# Voltage_Source.net
KiCad netlist of a schematic drawn in Altium Designer
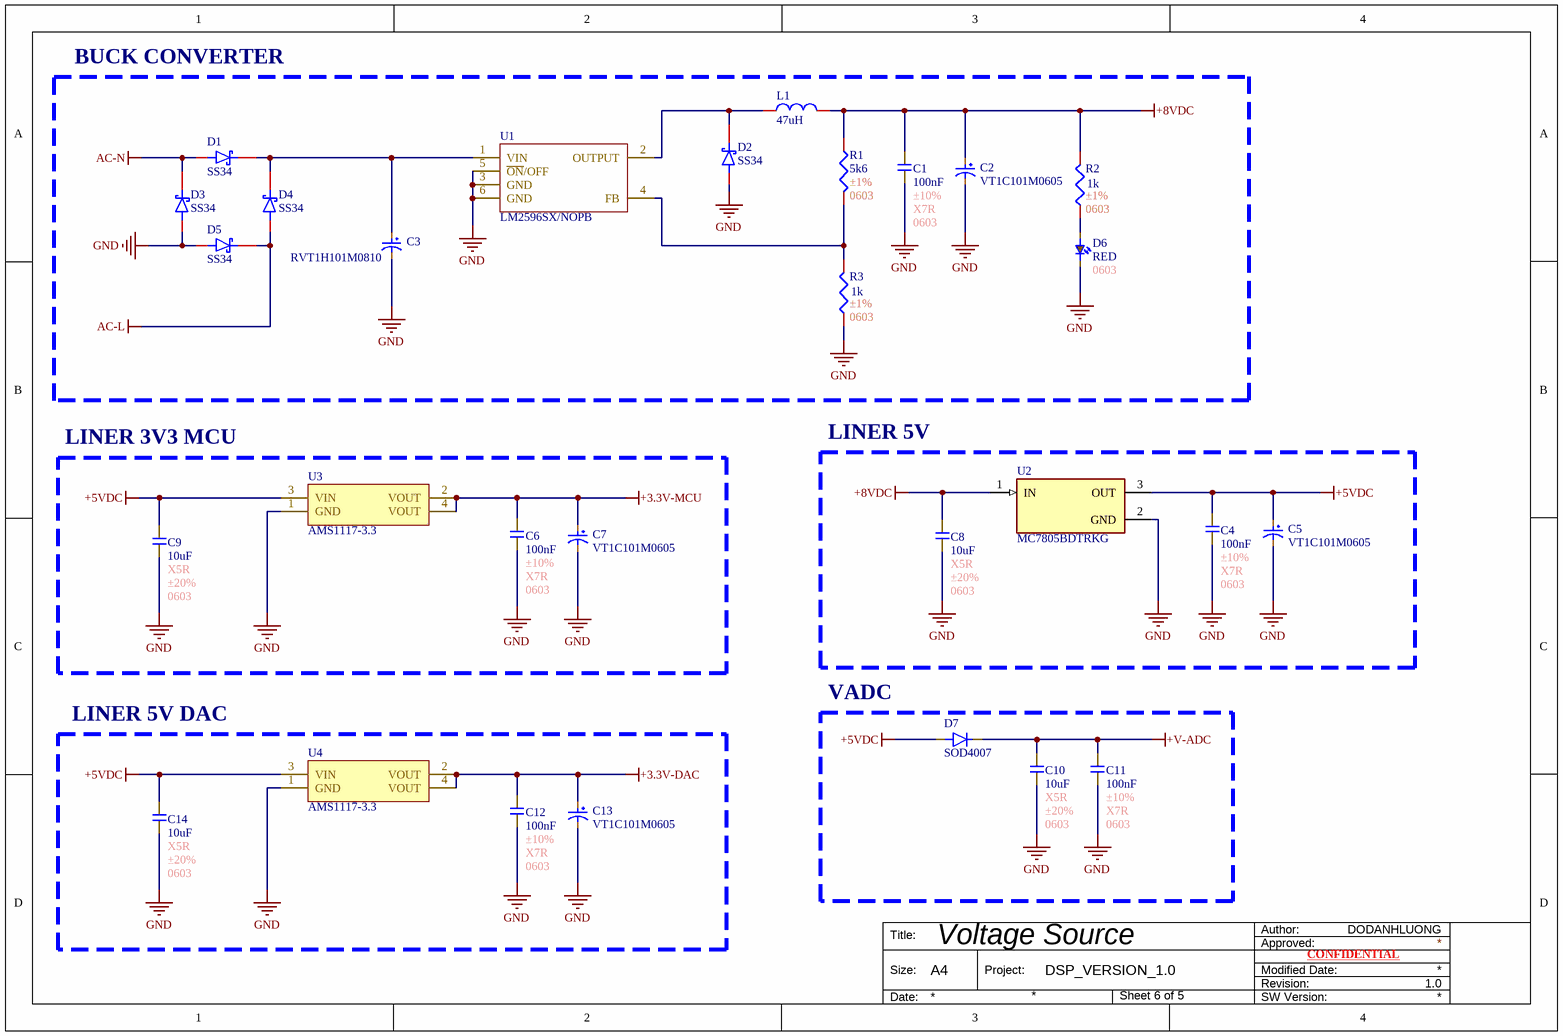
[diagram p0: Voltage Source.SchDoc]

(export (version "E")
  (design (tool "Eeschema 10.0.6"))
  (components
    (comp (ref "C1")
      (value "100nF")
      (footprint "C0603")
      (description "50V 100nF X7R ±10% 0603 Multilayer Ceramic Capacitors MLCC - SMD/SMT ROHS")
      (fields
        (field (name "MANUFACTURER") "YAGEO")
        (field (name "MFR. PART #") "CC0603KRX7R9BB104")
        (field (name "TOLERANCE") "±10%")
        (field (name "TEMPERATURE COEFFICIENT") "X7R")
        (field (name "PACKAGE") "0603")
      )
      (libsource (lib "DSP_VERSION_1.0") (part "C0603_100nF_±10%_X7R"))
    )
    (comp (ref "C2")
      (value "VT1C101M0605")
      (footprint "C_100uF_16V_Aluminum")
      (description "100uF 16V ±20% 63mA@120Hz SMD,D6.3xL5.4mm Aluminum Electrolytic Capacitors RoHS")
      (fields (field (name "MANUFACTURER") "ROQANG") (field (name "LCSC PART #") "C90273"))
      (libsource (lib "Capital") (part "C_100uF_16V_aluminum"))
    )
    (comp (ref "C3")
      (value "RVT1H101M0810")
      (footprint "C_100uF_Aluminum")
      (description "100uF 50V ±20% 146mA@120Hz SMD,D8xL10.2mm Aluminum Electrolytic Capacitors RoHS")
      (fields (field (name "MANUFACTURER") "ROQANG") (field (name "LCSC PART #") "C72480"))
      (libsource (lib "Capital") (part "C_100uF_aluminum"))
    )
    (comp (ref "C4")
      (value "100nF")
      (footprint "C0603")
      (description "50V 100nF X7R ±10% 0603 Multilayer Ceramic Capacitors MLCC - SMD/SMT ROHS")
      (fields
        (field (name "MANUFACTURER") "YAGEO")
        (field (name "MFR. PART #") "CC0603KRX7R9BB104")
        (field (name "TOLERANCE") "±10%")
        (field (name "TEMPERATURE COEFFICIENT") "X7R")
        (field (name "PACKAGE") "0603")
      )
      (libsource (lib "DSP_VERSION_1.0") (part "C0603_100nF_±10%_X7R"))
    )
    (comp (ref "C5")
      (value "VT1C101M0605")
      (footprint "C_100uF_16V_Aluminum")
      (description "100uF 16V ±20% 63mA@120Hz SMD,D6.3xL5.4mm Aluminum Electrolytic Capacitors RoHS")
      (fields (field (name "MANUFACTURER") "ROQANG") (field (name "LCSC PART #") "C90273"))
      (libsource (lib "Capital") (part "C_100uF_16V_aluminum"))
    )
    (comp (ref "C6")
      (value "100nF")
      (footprint "C0603")
      (description "50V 100nF X7R ±10% 0603 Multilayer Ceramic Capacitors MLCC - SMD/SMT ROHS")
      (fields
        (field (name "MANUFACTURER") "YAGEO")
        (field (name "MFR. PART #") "CC0603KRX7R9BB104")
        (field (name "TOLERANCE") "±10%")
        (field (name "TEMPERATURE COEFFICIENT") "X7R")
        (field (name "PACKAGE") "0603")
      )
      (libsource (lib "DSP_VERSION_1.0") (part "C0603_100nF_±10%_X7R"))
    )
    (comp (ref "C7")
      (value "VT1C101M0605")
      (footprint "C_100uF_16V_Aluminum")
      (description "100uF 16V ±20% 63mA@120Hz SMD,D6.3xL5.4mm Aluminum Electrolytic Capacitors RoHS")
      (fields (field (name "MANUFACTURER") "ROQANG") (field (name "LCSC PART #") "C90273"))
      (libsource (lib "Capital") (part "C_100uF_16V_aluminum"))
    )
    (comp (ref "C8")
      (value "10uF")
      (footprint "C0603")
      (description "25V 10uF X5R ±20% 0603 Multilayer Ceramic Capacitors MLCC - SMD/SMT ROHS")
      (fields
        (field (name "MANUFACTURER") "YAGEO")
        (field (name "MFR. PART #") "CC0603MRX5R8BB106")
        (field (name "TEMPERATURE COEFFICIENT") "X5R")
        (field (name "TOLERANCE") "±20%")
        (field (name "PACKAGE") "0603")
      )
      (libsource (lib "DSP_VERSION_1.0") (part "C0603_10uF_±10%_X7R"))
    )
    (comp (ref "C9")
      (value "10uF")
      (footprint "C0603")
      (description "25V 10uF X5R ±20% 0603 Multilayer Ceramic Capacitors MLCC - SMD/SMT ROHS")
      (fields
        (field (name "MANUFACTURER") "YAGEO")
        (field (name "MFR. PART #") "CC0603MRX5R8BB106")
        (field (name "TEMPERATURE COEFFICIENT") "X5R")
        (field (name "TOLERANCE") "±20%")
        (field (name "PACKAGE") "0603")
      )
      (libsource (lib "DSP_VERSION_1.0") (part "C0603_10uF_±10%_X7R"))
    )
    (comp (ref "C10")
      (value "10uF")
      (footprint "C0603")
      (description "25V 10uF X5R ±20% 0603 Multilayer Ceramic Capacitors MLCC - SMD/SMT ROHS")
      (fields
        (field (name "MANUFACTURER") "YAGEO")
        (field (name "MFR. PART #") "CC0603MRX5R8BB106")
        (field (name "TEMPERATURE COEFFICIENT") "X5R")
        (field (name "TOLERANCE") "±20%")
        (field (name "PACKAGE") "0603")
      )
      (libsource (lib "DSP_VERSION_1.0") (part "C0603_10uF_±10%_X7R"))
    )
    (comp (ref "C11")
      (value "100nF")
      (footprint "C0603")
      (description "50V 100nF X7R ±10% 0603 Multilayer Ceramic Capacitors MLCC - SMD/SMT ROHS")
      (fields
        (field (name "MANUFACTURER") "YAGEO")
        (field (name "MFR. PART #") "CC0603KRX7R9BB104")
        (field (name "TOLERANCE") "±10%")
        (field (name "TEMPERATURE COEFFICIENT") "X7R")
        (field (name "PACKAGE") "0603")
      )
      (libsource (lib "DSP_VERSION_1.0") (part "C0603_100nF_±10%_X7R"))
    )
    (comp (ref "C12")
      (value "100nF")
      (footprint "C0603")
      (description "50V 100nF X7R ±10% 0603 Multilayer Ceramic Capacitors MLCC - SMD/SMT ROHS")
      (fields
        (field (name "MANUFACTURER") "YAGEO")
        (field (name "MFR. PART #") "CC0603KRX7R9BB104")
        (field (name "TOLERANCE") "±10%")
        (field (name "TEMPERATURE COEFFICIENT") "X7R")
        (field (name "PACKAGE") "0603")
      )
      (libsource (lib "DSP_VERSION_1.0") (part "C0603_100nF_±10%_X7R"))
    )
    (comp (ref "C13")
      (value "VT1C101M0605")
      (footprint "C_100uF_16V_Aluminum")
      (description "100uF 16V ±20% 63mA@120Hz SMD,D6.3xL5.4mm Aluminum Electrolytic Capacitors RoHS")
      (fields (field (name "MANUFACTURER") "ROQANG") (field (name "LCSC PART #") "C90273"))
      (libsource (lib "Capital") (part "C_100uF_16V_aluminum"))
    )
    (comp (ref "C14")
      (value "10uF")
      (footprint "C0603")
      (description "25V 10uF X5R ±20% 0603 Multilayer Ceramic Capacitors MLCC - SMD/SMT ROHS")
      (fields
        (field (name "MANUFACTURER") "YAGEO")
        (field (name "MFR. PART #") "CC0603MRX5R8BB106")
        (field (name "TEMPERATURE COEFFICIENT") "X5R")
        (field (name "TOLERANCE") "±20%")
        (field (name "PACKAGE") "0603")
      )
      (libsource (lib "DSP_VERSION_1.0") (part "C0603_10uF_±10%_X7R"))
    )
    (comp (ref "D1")
      (value "SS34")
      (footprint "SS34")
      (description "40V Independent 3A 550mV@3A SMA(DO-214AC) Schottky Diodes ROHS")
      (fields
        (field (name "MANUFACTURER") "MDD(Microdiode Semiconductor)")
        (field (name "LCSC PART #") "C8678")
      )
      (libsource (lib "Diode") (part "SS34"))
    )
    (comp (ref "D2")
      (value "SS34")
      (footprint "SS34")
      (description "40V Independent 3A 550mV@3A SMA(DO-214AC) Schottky Diodes ROHS")
      (fields
        (field (name "MANUFACTURER") "MDD(Microdiode Semiconductor)")
        (field (name "LCSC PART #") "C8678")
      )
      (libsource (lib "Diode") (part "SS34"))
    )
    (comp (ref "D3")
      (value "SS34")
      (footprint "SS34")
      (description "40V Independent 3A 550mV@3A SMA(DO-214AC) Schottky Diodes ROHS")
      (fields
        (field (name "MANUFACTURER") "MDD(Microdiode Semiconductor)")
        (field (name "LCSC PART #") "C8678")
      )
      (libsource (lib "Diode") (part "SS34"))
    )
    (comp (ref "D4")
      (value "SS34")
      (footprint "SS34")
      (description "40V Independent 3A 550mV@3A SMA(DO-214AC) Schottky Diodes ROHS")
      (fields
        (field (name "MANUFACTURER") "MDD(Microdiode Semiconductor)")
        (field (name "LCSC PART #") "C8678")
      )
      (libsource (lib "Diode") (part "SS34"))
    )
    (comp (ref "D5")
      (value "SS34")
      (footprint "SS34")
      (description "40V Independent 3A 550mV@3A SMA(DO-214AC) Schottky Diodes ROHS")
      (fields
        (field (name "MANUFACTURER") "MDD(Microdiode Semiconductor)")
        (field (name "LCSC PART #") "C8678")
      )
      (libsource (lib "Diode") (part "SS34"))
    )
    (comp (ref "D6")
      (value "RED")
      (footprint "LED0603")
      (description "25mcd~40mcd Water Clear -40℃~+85℃ 624nm Red 120° 60mW 0402 LED Indication - Discrete ROHS")
      (fields
        (field (name "MANUFACTURER") "XINGLIGHT")
        (field (name "MFR. PART #") "XL-1005UGC")
        (field (name "PACKAGE") "0603")
      )
      (libsource (lib "LED") (part "D0603_RED"))
    )
    (comp (ref "D7")
      (value "SOD4007")
      (footprint "SOD4007")
      (description "1A Independent 1kV 1.1V@1A SOD-123FL Diodes - General Purpose ROHS")
      (fields
        (field (name "MANUFACTURER") "MDD(Microdiode Semiconductor)")
        (field (name "LCSC PART #") "C18124")
      )
      (libsource (lib "Diode") (part "SOD4007"))
    )
    (comp (ref "L1")
      (value "47uH")
      (footprint "CD43")
      (description "1.15A 10uH Unshielded Inductor ±20% SMD,4x4.5mm Power Inductors ROHS")
      (fields (field (name "MANUFACTURER") "ZE") (field (name "MFR. PART #") "CD43-100M"))
      (libsource (lib "Inductor") (part "CD4-10UH"))
    )
    (comp (ref "R1")
      (value "5k6")
      (footprint "R0603")
      (description "62.5mW Thick Film Resistor 50V ±1% ±200ppm/℃ 10Ω 0402 Chip Resistor - Surface Mount ROHS")
      (fields
        (field (name "MANUFACTURER") "YAGEO")
        (field (name "MFR. PART #") "RC0402FR-0710RL")
        (field (name "TOLERANCE") "±1%")
        (field (name "PACKAGE") "0603")
      )
      (libsource (lib "Resistor") (part "R0603_4k7Ω_±1%"))
    )
    (comp (ref "R2")
      (value "1k")
      (footprint "R0603")
      (description "62.5mW Thick Film Resistor 50V ±1% ±200ppm/℃ 10Ω 0402 Chip Resistor - Surface Mount ROHS")
      (fields
        (field (name "MANUFACTURER") "YAGEO")
        (field (name "MFR. PART #") "RC0402FR-0710RL")
        (field (name "TOLERANCE") "±1%")
        (field (name "PACKAGE") "0603")
      )
      (libsource (lib "Resistor") (part "R0603_4k7Ω_±1%"))
    )
    (comp (ref "R3")
      (value "1k")
      (footprint "R0603")
      (description "62.5mW Thick Film Resistor 50V ±1% ±200ppm/℃ 10Ω 0402 Chip Resistor - Surface Mount ROHS")
      (fields
        (field (name "MANUFACTURER") "YAGEO")
        (field (name "MFR. PART #") "RC0402FR-0710RL")
        (field (name "TOLERANCE") "±1%")
        (field (name "PACKAGE") "0603")
      )
      (libsource (lib "Resistor") (part "R0603_4k7Ω_±1%"))
    )
    (comp (ref "U1")
      (value "LM2596SX/NOPB")
      (footprint "LM2596SX-5.0/NOPB")
      (description "150kHz Buck Fixed 1 TO-263-5 Voltage Regulators - DC DC Switching Regulators RoHS")
      (fields (field (name "MANUFACTURER") "TI") (field (name "LCSC PART #") "C10002"))
      (libsource (lib "IC") (part "LM2596SX/NOPB"))
    )
    (comp (ref "U2")
      (value "MC7805BDTRKG")
      (footprint "7805")
      (fields (field (name "MANUFACTURER") "onsemi") (field (name "LCSC PART #") "C110908"))
      (libsource (lib "IC") (part "7805"))
    )
    (comp (ref "U3")
      (value "AMS1117-3.3")
      (footprint "AMS1117-3.3")
      (fields
        (field (name "MANUFACTURER") "Advanced Monolithic Systems")
        (field (name "LCSC PART #") "C6186")
      )
      (libsource (lib "IC") (part "AMS1117-3.3"))
    )
    (comp (ref "U4")
      (value "AMS1117-3.3")
      (footprint "AMS1117-3.3")
      (fields
        (field (name "MANUFACTURER") "Advanced Monolithic Systems")
        (field (name "LCSC PART #") "C6186")
      )
      (libsource (lib "IC") (part "AMS1117-3.3"))
    )
  )
  (nets
    (net (code "1") (name "+3.3V-DAC") (class "Default")
      (node (ref "C12") (pin "2") (pinfunction "2_2") (pintype "passive"))
      (node (ref "C13") (pin "1") (pinfunction "1_1") (pintype "passive"))
      (node (ref "U4") (pin "2") (pinfunction "VOUT_2") (pintype "passive"))
      (node (ref "U4") (pin "4") (pinfunction "VOUT_4") (pintype "passive"))
    )
    (net (code "2") (name "+3.3V-MCU") (class "Default")
      (node (ref "C6") (pin "2") (pinfunction "2_2") (pintype "passive"))
      (node (ref "C7") (pin "1") (pinfunction "1_1") (pintype "passive"))
      (node (ref "U3") (pin "2") (pinfunction "VOUT_2") (pintype "passive"))
      (node (ref "U3") (pin "4") (pinfunction "VOUT_4") (pintype "passive"))
    )
    (net (code "3") (name "+5VDC") (class "Default")
      (node (ref "C14") (pin "2") (pinfunction "2_2") (pintype "passive"))
      (node (ref "C4") (pin "2") (pinfunction "2_2") (pintype "passive"))
      (node (ref "C5") (pin "1") (pinfunction "1_1") (pintype "passive"))
      (node (ref "C9") (pin "2") (pinfunction "2_2") (pintype "passive"))
      (node (ref "D7") (pin "2") (pinfunction "A_2") (pintype "passive"))
      (node (ref "U2") (pin "3") (pinfunction "OUT_3") (pintype "passive"))
      (node (ref "U3") (pin "3") (pinfunction "VIN_3") (pintype "passive"))
      (node (ref "U4") (pin "3") (pinfunction "VIN_3") (pintype "passive"))
    )
    (net (code "4") (name "+8VDC") (class "Default")
      (node (ref "C1") (pin "2") (pinfunction "2_2") (pintype "passive"))
      (node (ref "C2") (pin "1") (pinfunction "1_1") (pintype "passive"))
      (node (ref "C8") (pin "2") (pinfunction "2_2") (pintype "passive"))
      (node (ref "L1") (pin "2") (pinfunction "2_2") (pintype "passive"))
      (node (ref "R1") (pin "1") (pinfunction "1_1") (pintype "passive"))
      (node (ref "R2") (pin "2") (pinfunction "2_2") (pintype "passive"))
      (node (ref "U2") (pin "1") (pinfunction "IN_1") (pintype "input"))
    )
    (net (code "5") (name "+V-ADC") (class "Default")
      (node (ref "C10") (pin "2") (pinfunction "2_2") (pintype "passive"))
      (node (ref "C11") (pin "2") (pinfunction "2_2") (pintype "passive"))
      (node (ref "D7") (pin "1") (pinfunction "C_1") (pintype "passive"))
    )
    (net (code "6") (name "AC-L") (class "Default")
      (node (ref "D4") (pin "2") (pinfunction "2_2") (pintype "passive"))
      (node (ref "D5") (pin "1") (pinfunction "1_1") (pintype "passive"))
    )
    (net (code "7") (name "AC-N") (class "Default")
      (node (ref "D1") (pin "2") (pinfunction "2_2") (pintype "passive"))
      (node (ref "D3") (pin "1") (pinfunction "1_1") (pintype "passive"))
    )
    (net (code "8") (name "GND") (class "Default")
      (node (ref "C1") (pin "1") (pinfunction "1_1") (pintype "passive"))
      (node (ref "C10") (pin "1") (pinfunction "1_1") (pintype "passive"))
      (node (ref "C11") (pin "1") (pinfunction "1_1") (pintype "passive"))
      (node (ref "C12") (pin "1") (pinfunction "1_1") (pintype "passive"))
      (node (ref "C13") (pin "2") (pinfunction "2_2") (pintype "passive"))
      (node (ref "C14") (pin "1") (pinfunction "1_1") (pintype "passive"))
      (node (ref "C2") (pin "2") (pinfunction "2_2") (pintype "passive"))
      (node (ref "C3") (pin "2") (pinfunction "2_2") (pintype "passive"))
      (node (ref "C4") (pin "1") (pinfunction "1_1") (pintype "passive"))
      (node (ref "C5") (pin "2") (pinfunction "2_2") (pintype "passive"))
      (node (ref "C6") (pin "1") (pinfunction "1_1") (pintype "passive"))
      (node (ref "C7") (pin "2") (pinfunction "2_2") (pintype "passive"))
      (node (ref "C8") (pin "1") (pinfunction "1_1") (pintype "passive"))
      (node (ref "C9") (pin "1") (pinfunction "1_1") (pintype "passive"))
      (node (ref "D2") (pin "2") (pinfunction "2_2") (pintype "passive"))
      (node (ref "D3") (pin "2") (pinfunction "2_2") (pintype "passive"))
      (node (ref "D5") (pin "2") (pinfunction "2_2") (pintype "passive"))
      (node (ref "D6") (pin "1") (pinfunction "1_1") (pintype "passive"))
      (node (ref "R3") (pin "1") (pinfunction "1_1") (pintype "passive"))
      (node (ref "U1") (pin "3") (pinfunction "GND_3") (pintype "passive"))
      (node (ref "U1") (pin "5") (pinfunction "~{ON}/OFF_5") (pintype "passive"))
      (node (ref "U1") (pin "6") (pinfunction "GND_6") (pintype "passive"))
      (node (ref "U2") (pin "2") (pinfunction "GND_2") (pintype "power_in"))
      (node (ref "U3") (pin "1") (pinfunction "GND_1") (pintype "passive"))
      (node (ref "U4") (pin "1") (pinfunction "GND_1") (pintype "passive"))
    )
    (net (code "9") (name "Net-(D6-Pad2)") (class "Default")
      (node (ref "D6") (pin "2") (pinfunction "2_2") (pintype "passive"))
      (node (ref "R2") (pin "1") (pinfunction "1_1") (pintype "passive"))
    )
    (net (code "10") (name "Net-(U1-FB)") (class "Default")
      (node (ref "R1") (pin "2") (pinfunction "2_2") (pintype "passive"))
      (node (ref "R3") (pin "2") (pinfunction "2_2") (pintype "passive"))
      (node (ref "U1") (pin "4") (pinfunction "FB_4") (pintype "passive"))
    )
    (net (code "11") (name "Net-(U1-OUTPUT)") (class "Default")
      (node (ref "D2") (pin "1") (pinfunction "1_1") (pintype "passive"))
      (node (ref "L1") (pin "1") (pinfunction "1_1") (pintype "passive"))
      (node (ref "U1") (pin "2") (pinfunction "OUTPUT_2") (pintype "passive"))
    )
    (net (code "12") (name "Net-(U1-VIN)") (class "Default")
      (node (ref "C3") (pin "1") (pinfunction "1_1") (pintype "passive"))
      (node (ref "D1") (pin "1") (pinfunction "1_1") (pintype "passive"))
      (node (ref "D4") (pin "1") (pinfunction "1_1") (pintype "passive"))
      (node (ref "U1") (pin "1") (pinfunction "VIN_1") (pintype "passive"))
    )
  )
)
